# Supply_0_V1_01.net
KiCad netlist of a schematic drawn in Altium Designer
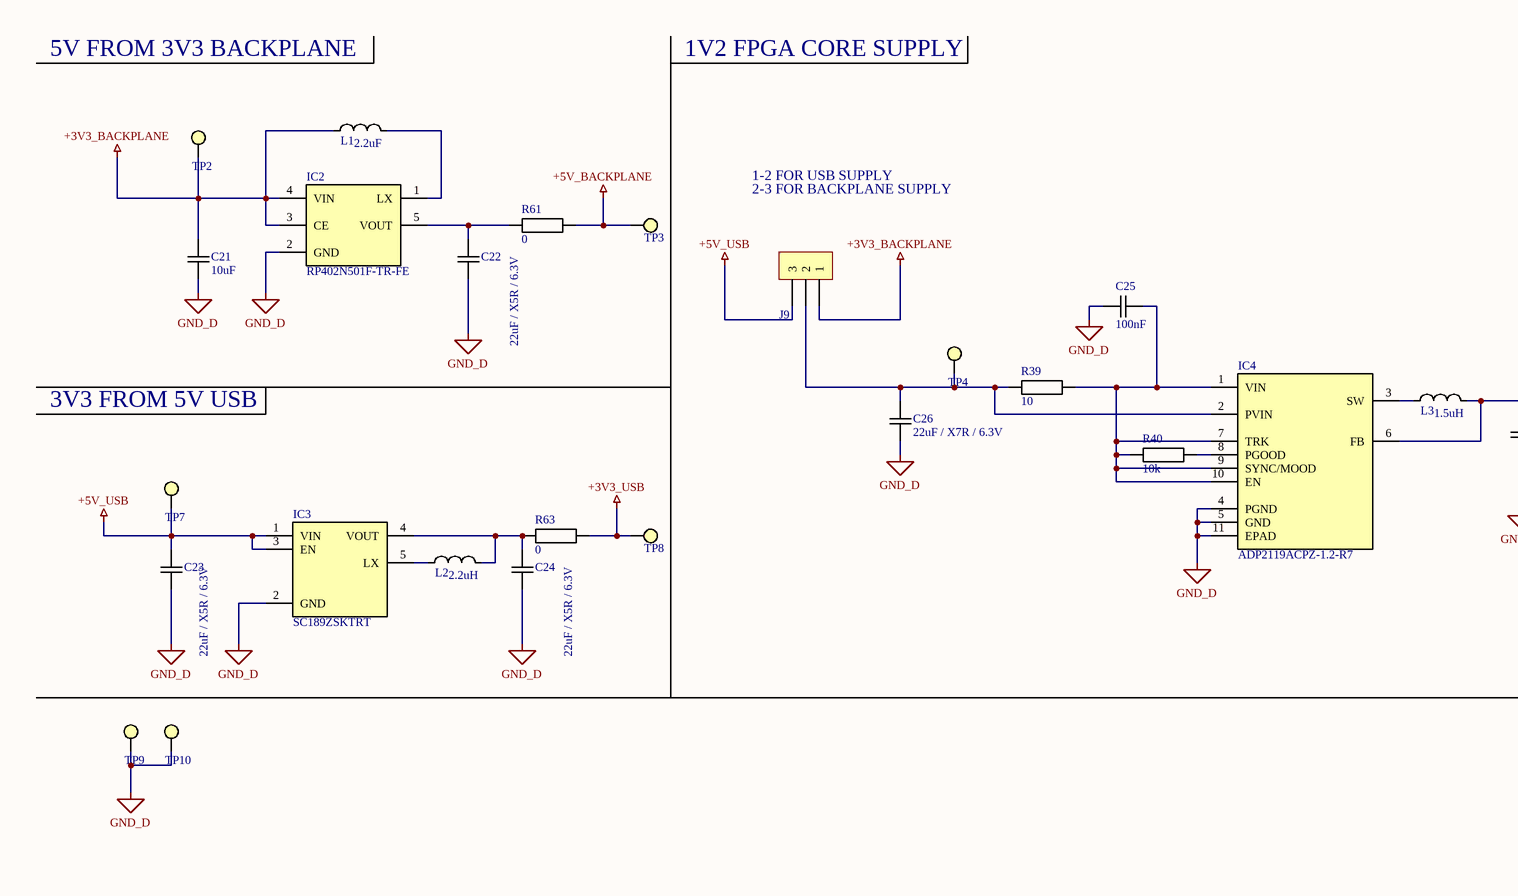
[diagram p0: Supply_0_V1_01.SchDoc, left]
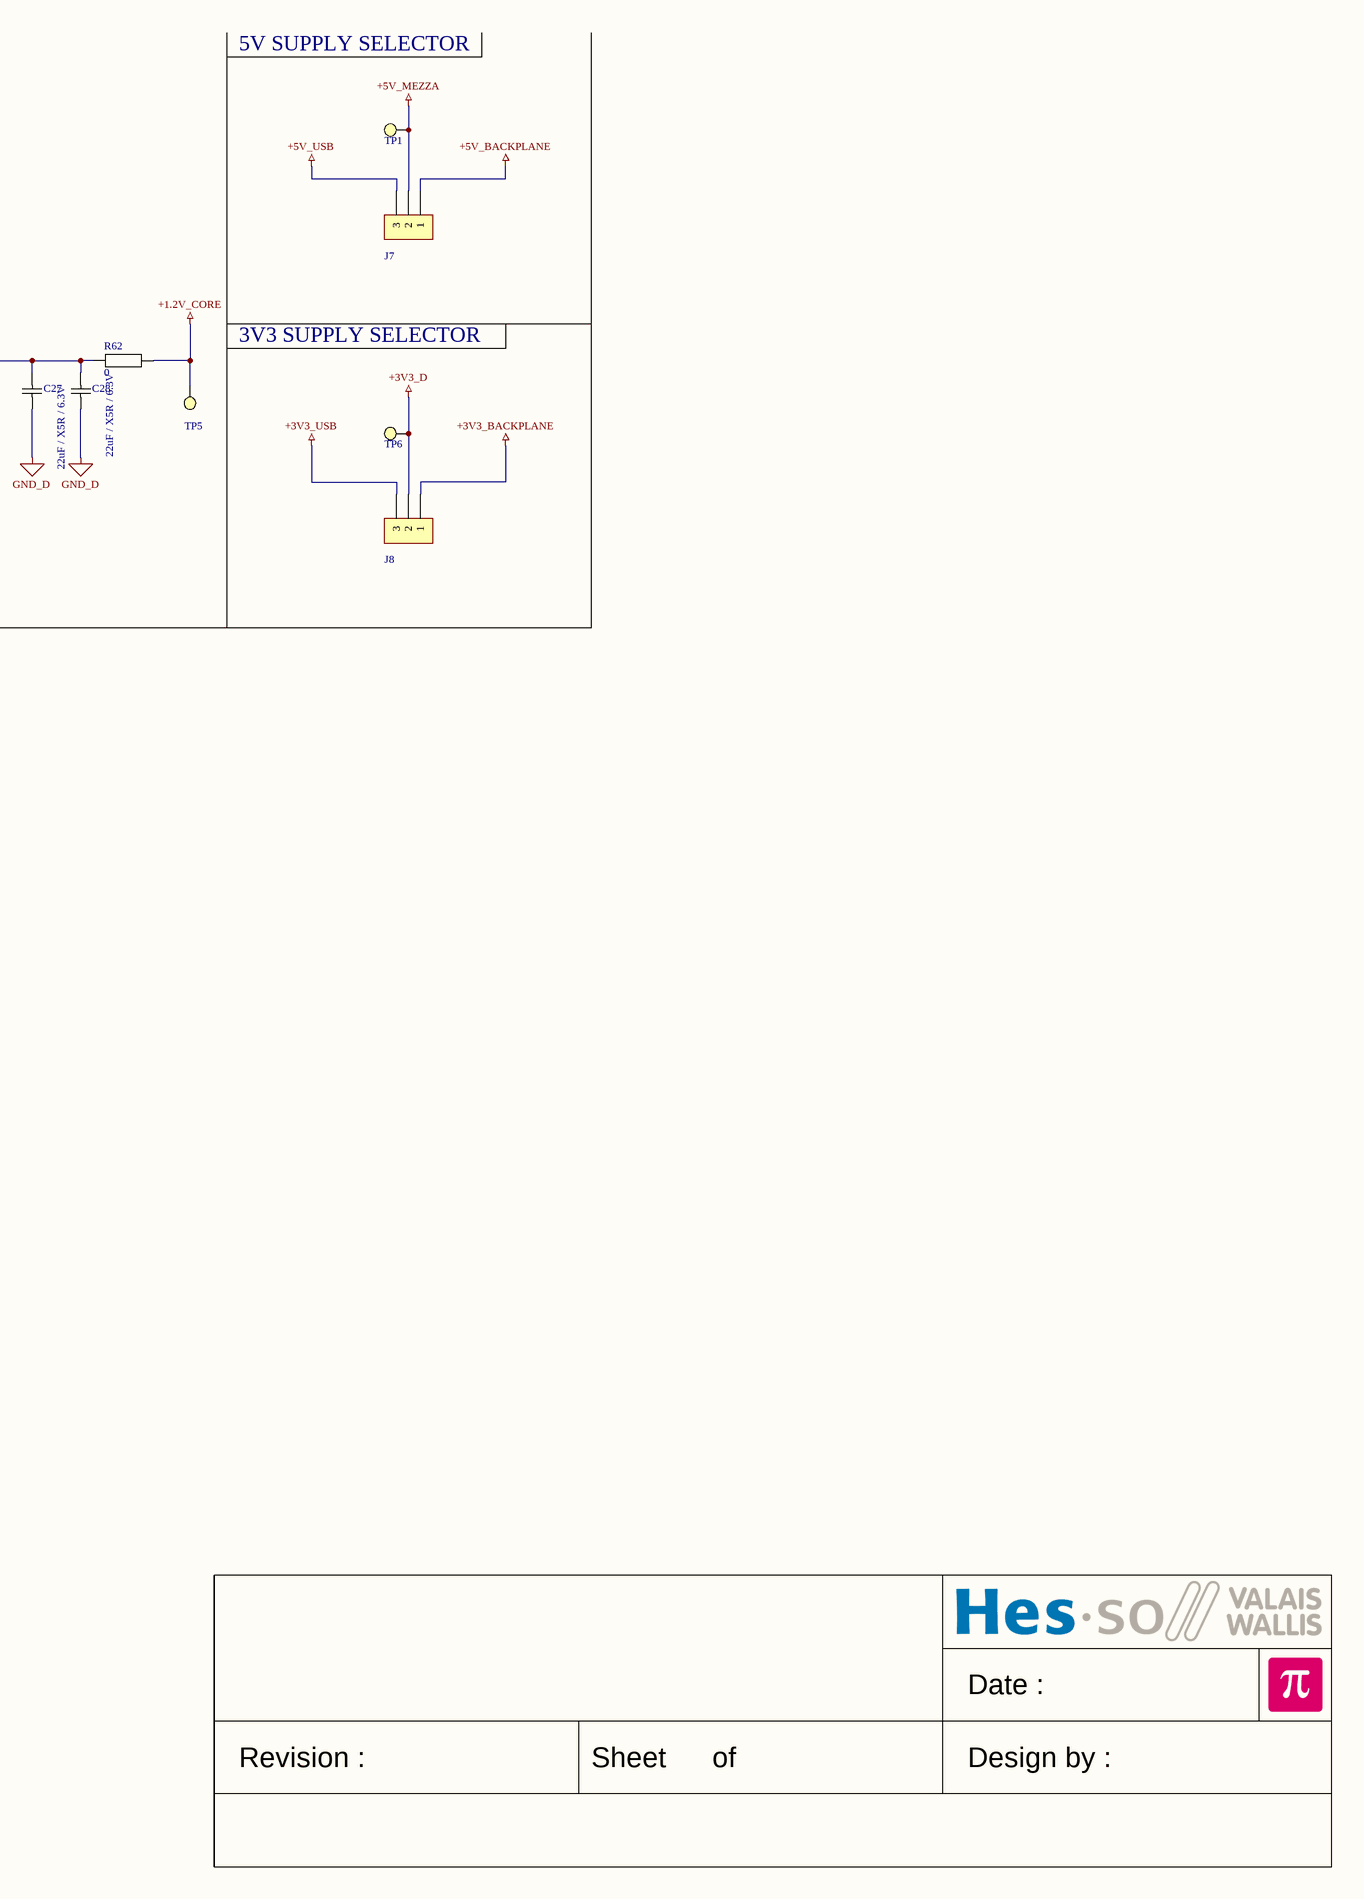
[diagram p1: Supply_0_V1_01.SchDoc, right]

(export (version "E")
  (design (tool "Eeschema 10.0.6"))
  (components
    (comp (ref "C21")
      (value "10uF")
      (footprint "CAPACITOR 2012 REFLOW")
      (description "Capacitor")
      (libsource (lib "Capacitor") (part "Capacitor"))
    )
    (comp (ref "C22")
      (value "22uF / X5R / 6.3V")
      (footprint "CAPACITOR 2012 REFLOW")
      (description "Capacitor")
      (libsource (lib "Capacitor") (part "Capacitor"))
    )
    (comp (ref "C23")
      (value "22uF / X5R / 6.3V")
      (footprint "CAPACITOR 2012 REFLOW")
      (description "Capacitor")
      (libsource (lib "Capacitor") (part "Capacitor"))
    )
    (comp (ref "C24")
      (value "22uF / X5R / 6.3V")
      (footprint "CAPACITOR 2012 REFLOW")
      (description "Capacitor")
      (libsource (lib "Capacitor") (part "Capacitor"))
    )
    (comp (ref "C25")
      (value "100nF")
      (footprint "CAPACITOR 1608 REFLOW")
      (description "Capacitor")
      (libsource (lib "Capacitor") (part "Capacitor"))
    )
    (comp (ref "C26")
      (value "22uF / X7R / 6.3V")
      (footprint "CAPACITOR 2012 REFLOW")
      (description "Capacitor")
      (libsource (lib "Capacitor") (part "Capacitor"))
    )
    (comp (ref "C27")
      (value "22uF / X5R / 6.3V")
      (footprint "CAPACITOR 2012 REFLOW")
      (description "Capacitor")
      (libsource (lib "Capacitor") (part "Capacitor"))
    )
    (comp (ref "C28")
      (value "22uF / X5R / 6.3V")
      (footprint "CAPACITOR 2012 REFLOW")
      (description "Capacitor")
      (libsource (lib "Capacitor") (part "Capacitor"))
    )
    (comp (ref "IC2")
      (value "RP402N501F-TR-FE")
      (footprint "SamacSys:SOT95P280X130-5N")
      (description "Integrated Circuit")
      (fields (field (name "MOUSER PART NUMBER") "848-RP402N501F-TR-FE"))
      (libsource (lib "SamacSys") (part "RP402N501F-TR-FE"))
    )
    (comp (ref "IC3")
      (value "SC189ZSKTRT")
      (footprint "SamacSys:SOT95P280X145-5N")
      (description "Integrated Circuit")
      (fields (field (name "MOUSER PART NUMBER") "947-SC189ZSKTRT"))
      (libsource (lib "SamacSys") (part "SC189ZSKTRT"))
    )
    (comp (ref "IC4")
      (value "ADP2119ACPZ-1.2-R7")
      (footprint "SamacSys:SON50P300X300X85-11N")
      (description "Integrated Circuit")
      (fields (field (name "MOUSER PART NUMBER") "584-ADP2119ACPZ1.2R7"))
      (libsource (lib "SamacSys") (part "ADP2119ACPZ-1.2-R7"))
    )
    (comp (ref "J7")
      (value "*")
      (footprint "PinHeader1x3 P2.54")
      (description "Plug connector")
      (libsource (lib "") (part "PinHeader1x3_1"))
    )
    (comp (ref "J8")
      (value "*")
      (footprint "PinHeader1x3 P2.54")
      (description "Plug connector")
      (libsource (lib "") (part "PinHeader1x3_1"))
    )
    (comp (ref "J9")
      (value "*")
      (footprint "PinHeader1x3 P2.54")
      (description "Plug connector")
      (libsource (lib "PinHeader") (part "PinHeader1x3"))
    )
    (comp (ref "L1")
      (value "2.2uF")
      (footprint "TDK VLCF5020-1")
      (description "Inductor")
      (libsource (lib "Inductor") (part "Inductor"))
    )
    (comp (ref "L2")
      (value "2.2uH")
      (footprint "TDK VLCF5020-1")
      (description "Inductor")
      (libsource (lib "Inductor") (part "Inductor"))
    )
    (comp (ref "L3")
      (value "1.5uH")
      (footprint "TDK VLCF5020-1")
      (description "Inductor")
      (libsource (lib "Inductor") (part "Inductor"))
    )
    (comp (ref "R39")
      (value "10")
      (footprint "RESISTOR 2012 REFLOW")
      (description "Resistor 1% 50V 125mW 2012(0805)")
      (libsource (lib "Resistor") (part "Resistor"))
    )
    (comp (ref "R40")
      (value "10k")
      (footprint "RESISTOR 1608 REFLOW")
      (description "Resistor 1% 50V 125mW 2012(0805)")
      (libsource (lib "Resistor") (part "Resistor"))
    )
    (comp (ref "R61")
      (value "0")
      (footprint "RESISTOR 1608 REFLOW")
      (description "Resistor 1% 50V 100mW 1608(0603)")
      (libsource (lib "Resistor") (part "Resistor"))
    )
    (comp (ref "R62")
      (value "0")
      (footprint "RESISTOR 1608 REFLOW")
      (description "Resistor 1% 50V 100mW 1608(0603)")
      (libsource (lib "Resistor") (part "Resistor"))
    )
    (comp (ref "R63")
      (value "0")
      (footprint "RESISTOR 1608 REFLOW")
      (description "Resistor 1% 50V 100mW 1608(0603)")
      (libsource (lib "Resistor") (part "Resistor"))
    )
    (comp (ref "TP1")
      (value "*")
      (footprint "Test Point Keystone Miniature RED")
      (description "Test Point")
      (libsource (lib "Testpoint") (part "Test Point"))
    )
    (comp (ref "TP2")
      (value "*")
      (footprint "Test Point Keystone Miniature RED")
      (description "Test Point")
      (libsource (lib "Testpoint") (part "Test Point"))
    )
    (comp (ref "TP3")
      (value "*")
      (footprint "Test Point Keystone Miniature RED")
      (description "Test Point")
      (libsource (lib "Testpoint") (part "Test Point"))
    )
    (comp (ref "TP4")
      (value "*")
      (footprint "Test Point Keystone Miniature RED")
      (description "Test Point")
      (libsource (lib "Testpoint") (part "Test Point"))
    )
    (comp (ref "TP5")
      (value "*")
      (footprint "Test Point Keystone Miniature RED")
      (description "Test Point")
      (libsource (lib "Testpoint") (part "Test Point"))
    )
    (comp (ref "TP6")
      (value "*")
      (footprint "Test Point Keystone Miniature RED")
      (description "Test Point")
      (libsource (lib "Testpoint") (part "Test Point"))
    )
    (comp (ref "TP7")
      (value "*")
      (footprint "Test Point Keystone Miniature RED")
      (description "Test Point")
      (libsource (lib "Testpoint") (part "Test Point"))
    )
    (comp (ref "TP8")
      (value "*")
      (footprint "Test Point Keystone Miniature RED")
      (description "Test Point")
      (libsource (lib "Testpoint") (part "Test Point"))
    )
    (comp (ref "TP9")
      (value "*")
      (footprint "Test Point Keystone Miniature BLACK")
      (description "Test Point")
      (libsource (lib "Testpoint") (part "Test Point"))
    )
    (comp (ref "TP10")
      (value "*")
      (footprint "Test Point Keystone Miniature BLACK")
      (description "Test Point")
      (libsource (lib "Testpoint") (part "Test Point"))
    )
  )
  (nets
    (net (code "1") (name "+1.2V_CORE") (class "Default")
      (node (ref "R62") (pin "2") (pinfunction "2_2") (pintype "passive"))
      (node (ref "TP5") (pin "1") (pinfunction "1_1") (pintype "passive"))
    )
    (net (code "2") (name "+3V3_BACKPLANE") (class "Default")
      (node (ref "C21") (pin "2") (pinfunction "2_2") (pintype "passive"))
      (node (ref "IC2") (pin "3") (pinfunction "CE_3") (pintype "passive"))
      (node (ref "IC2") (pin "4") (pinfunction "VIN_4") (pintype "passive"))
      (node (ref "J8") (pin "1") (pinfunction "1_1") (pintype "passive"))
      (node (ref "J9") (pin "1") (pinfunction "1_1") (pintype "passive"))
      (node (ref "L1") (pin "1") (pinfunction "1_1") (pintype "passive"))
      (node (ref "TP2") (pin "1") (pinfunction "1_1") (pintype "passive"))
    )
    (net (code "3") (name "+3V3_D") (class "Default")
      (node (ref "J8") (pin "2") (pinfunction "2_2") (pintype "passive"))
      (node (ref "TP6") (pin "1") (pinfunction "1_1") (pintype "passive"))
    )
    (net (code "4") (name "+3V3_USB") (class "Default")
      (node (ref "J8") (pin "3") (pinfunction "3_3") (pintype "passive"))
      (node (ref "R63") (pin "2") (pinfunction "2_2") (pintype "passive"))
      (node (ref "TP8") (pin "1") (pinfunction "1_1") (pintype "passive"))
    )
    (net (code "5") (name "+5V_BACKPLANE") (class "Default")
      (node (ref "J7") (pin "1") (pinfunction "1_1") (pintype "passive"))
      (node (ref "R61") (pin "2") (pinfunction "2_2") (pintype "passive"))
      (node (ref "TP3") (pin "1") (pinfunction "1_1") (pintype "passive"))
    )
    (net (code "6") (name "+5V_MEZZA") (class "Default")
      (node (ref "J7") (pin "2") (pinfunction "2_2") (pintype "passive"))
      (node (ref "TP1") (pin "1") (pinfunction "1_1") (pintype "passive"))
    )
    (net (code "7") (name "+5V_USB") (class "Default")
      (node (ref "C23") (pin "2") (pinfunction "2_2") (pintype "passive"))
      (node (ref "IC3") (pin "1") (pinfunction "VIN_1") (pintype "passive"))
      (node (ref "IC3") (pin "3") (pinfunction "EN_3") (pintype "passive"))
      (node (ref "J7") (pin "3") (pinfunction "3_3") (pintype "passive"))
      (node (ref "J9") (pin "3") (pinfunction "3_3") (pintype "passive"))
      (node (ref "TP7") (pin "1") (pinfunction "1_1") (pintype "passive"))
    )
    (net (code "8") (name "GND_D") (class "Default")
      (node (ref "C21") (pin "1") (pinfunction "1_1") (pintype "passive"))
      (node (ref "C22") (pin "1") (pinfunction "1_1") (pintype "passive"))
      (node (ref "C23") (pin "1") (pinfunction "1_1") (pintype "passive"))
      (node (ref "C24") (pin "1") (pinfunction "1_1") (pintype "passive"))
      (node (ref "C25") (pin "2") (pinfunction "2_2") (pintype "passive"))
      (node (ref "C26") (pin "1") (pinfunction "1_1") (pintype "passive"))
      (node (ref "C27") (pin "1") (pinfunction "1_1") (pintype "passive"))
      (node (ref "C28") (pin "1") (pinfunction "1_1") (pintype "passive"))
      (node (ref "IC2") (pin "2") (pinfunction "GND_2") (pintype "passive"))
      (node (ref "IC3") (pin "2") (pinfunction "GND_2") (pintype "passive"))
      (node (ref "IC4") (pin "11") (pinfunction "EPAD_11") (pintype "passive"))
      (node (ref "IC4") (pin "4") (pinfunction "PGND_4") (pintype "passive"))
      (node (ref "IC4") (pin "5") (pinfunction "GND_5") (pintype "passive"))
      (node (ref "TP10") (pin "1") (pinfunction "1_1") (pintype "passive"))
      (node (ref "TP9") (pin "1") (pinfunction "1_1") (pintype "passive"))
    )
    (net (code "9") (name "Net-(IC2-LX)") (class "Default")
      (node (ref "IC2") (pin "1") (pinfunction "LX_1") (pintype "passive"))
      (node (ref "L1") (pin "2") (pinfunction "2_2") (pintype "passive"))
    )
    (net (code "10") (name "Net-(IC2-VOUT)") (class "Default")
      (node (ref "C22") (pin "2") (pinfunction "2_2") (pintype "passive"))
      (node (ref "IC2") (pin "5") (pinfunction "VOUT_5") (pintype "passive"))
      (node (ref "R61") (pin "1") (pinfunction "1_1") (pintype "passive"))
    )
    (net (code "11") (name "Net-(IC3-LX)") (class "Default")
      (node (ref "IC3") (pin "5") (pinfunction "LX_5") (pintype "passive"))
      (node (ref "L2") (pin "1") (pinfunction "1_1") (pintype "passive"))
    )
    (net (code "12") (name "Net-(IC3-VOUT)") (class "Default")
      (node (ref "C24") (pin "2") (pinfunction "2_2") (pintype "passive"))
      (node (ref "IC3") (pin "4") (pinfunction "VOUT_4") (pintype "passive"))
      (node (ref "L2") (pin "2") (pinfunction "2_2") (pintype "passive"))
      (node (ref "R63") (pin "1") (pinfunction "1_1") (pintype "passive"))
    )
    (net (code "13") (name "Net-(IC4-EN)") (class "Default")
      (node (ref "C25") (pin "1") (pinfunction "1_1") (pintype "passive"))
      (node (ref "IC4") (pin "1") (pinfunction "VIN_1") (pintype "passive"))
      (node (ref "IC4") (pin "10") (pinfunction "EN_10") (pintype "passive"))
      (node (ref "IC4") (pin "7") (pinfunction "TRK_7") (pintype "passive"))
      (node (ref "IC4") (pin "9") (pinfunction "SYNC/MOOD_9") (pintype "passive"))
      (node (ref "R39") (pin "1") (pinfunction "1_1") (pintype "passive"))
      (node (ref "R40") (pin "2") (pinfunction "2_2") (pintype "passive"))
    )
    (net (code "14") (name "Net-(IC4-FB)") (class "Default")
      (node (ref "C27") (pin "2") (pinfunction "2_2") (pintype "passive"))
      (node (ref "C28") (pin "2") (pinfunction "2_2") (pintype "passive"))
      (node (ref "IC4") (pin "6") (pinfunction "FB_6") (pintype "passive"))
      (node (ref "L3") (pin "2") (pinfunction "2_2") (pintype "passive"))
      (node (ref "R62") (pin "1") (pinfunction "1_1") (pintype "passive"))
    )
    (net (code "15") (name "Net-(IC4-PGOOD)") (class "Default")
      (node (ref "IC4") (pin "8") (pinfunction "PGOOD_8") (pintype "passive"))
      (node (ref "R40") (pin "1") (pinfunction "1_1") (pintype "passive"))
    )
    (net (code "16") (name "Net-(IC4-PVIN)") (class "Default")
      (node (ref "C26") (pin "2") (pinfunction "2_2") (pintype "passive"))
      (node (ref "IC4") (pin "2") (pinfunction "PVIN_2") (pintype "passive"))
      (node (ref "J9") (pin "2") (pinfunction "2_2") (pintype "passive"))
      (node (ref "R39") (pin "2") (pinfunction "2_2") (pintype "passive"))
      (node (ref "TP4") (pin "1") (pinfunction "1_1") (pintype "passive"))
    )
    (net (code "17") (name "Net-(IC4-SW)") (class "Default")
      (node (ref "IC4") (pin "3") (pinfunction "SW_3") (pintype "passive"))
      (node (ref "L3") (pin "1") (pinfunction "1_1") (pintype "passive"))
    )
  )
)
